# bGeigieNanoKit_V1_0r4.net
KiCad netlist of a schematic drawn in EAGLE
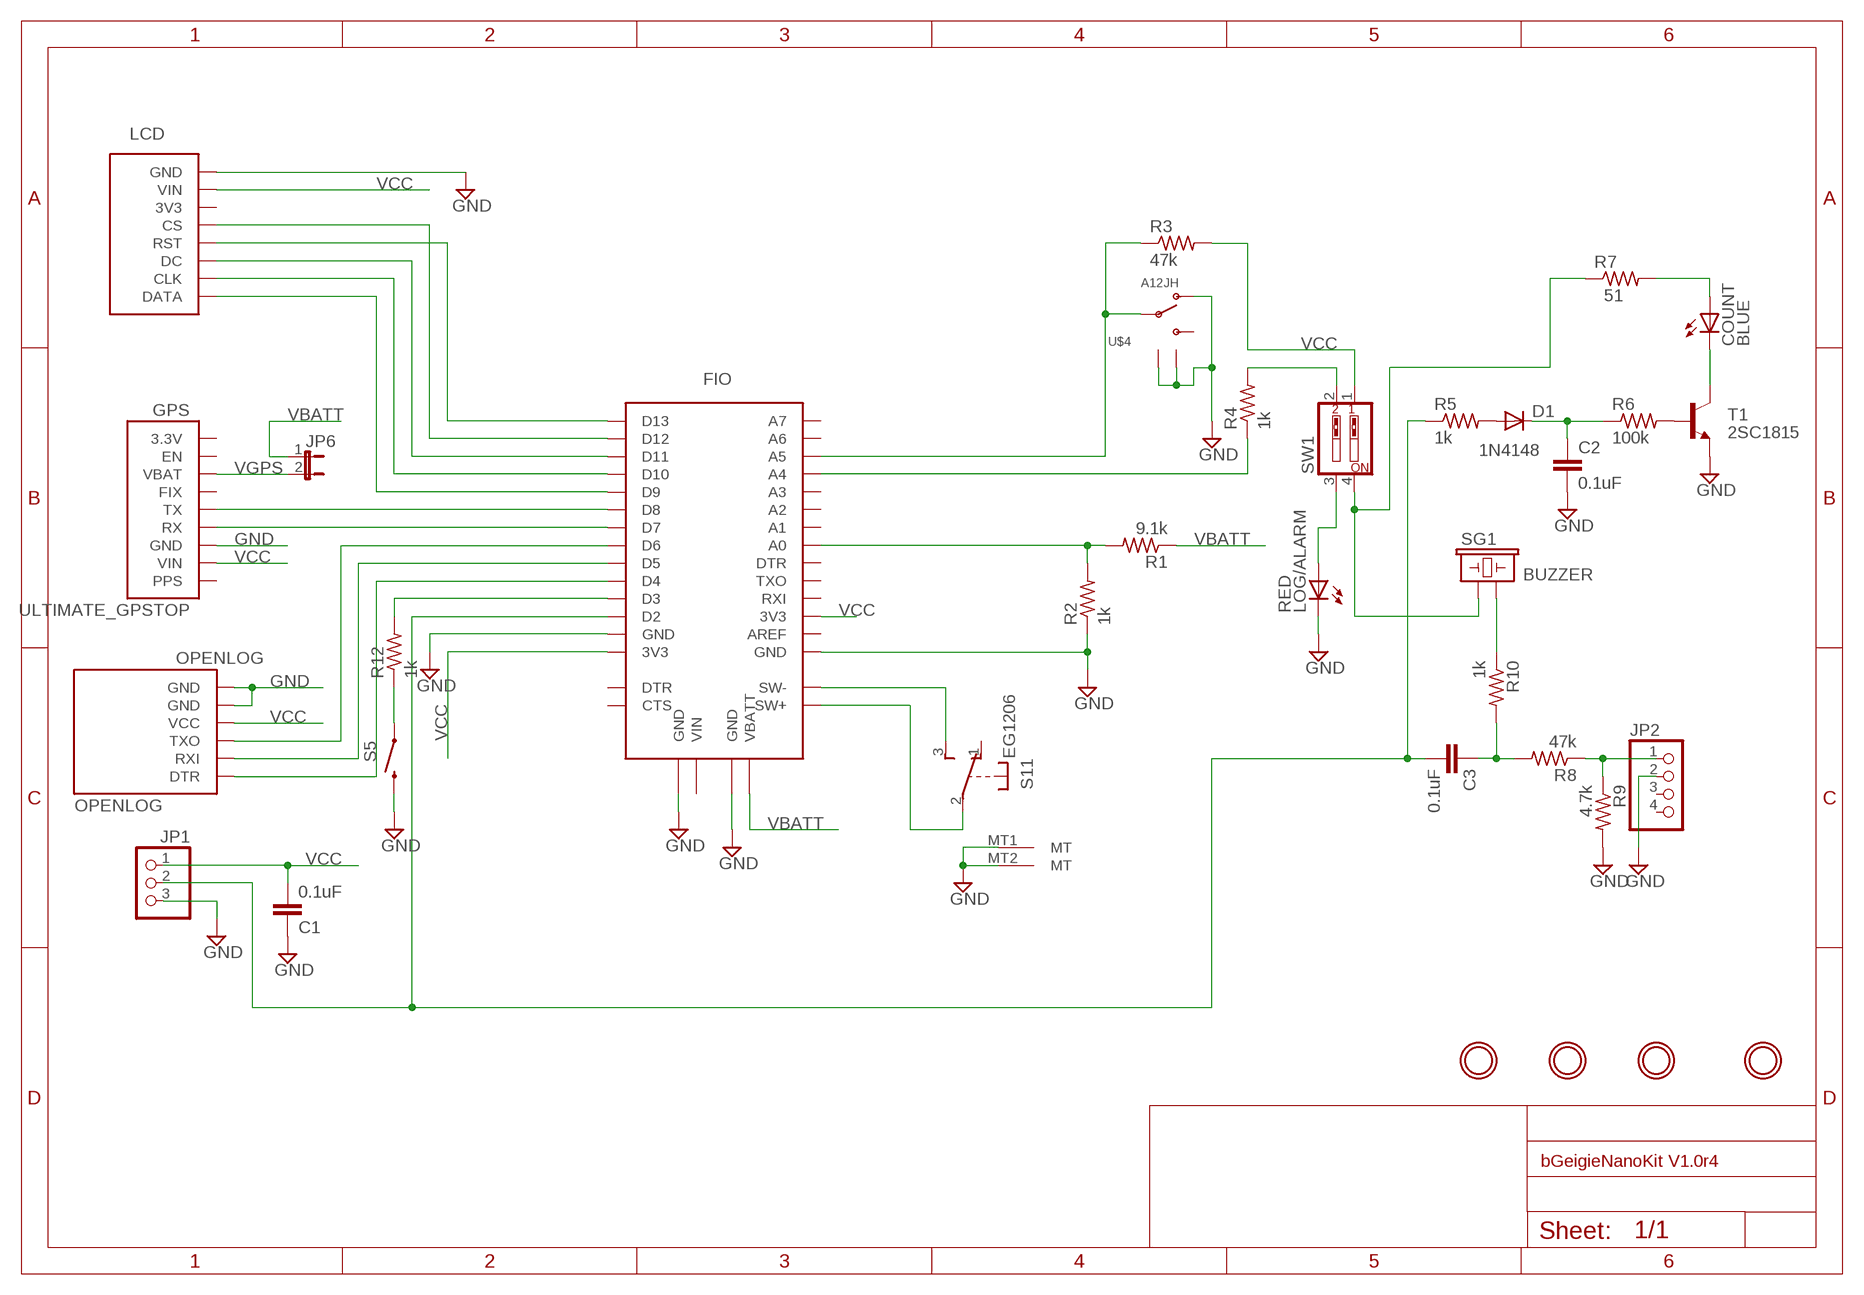
[diagram p0: schematic, sheet 1]

(export (version "E")
  (design (tool "Eeschema 10.0.6"))
  (components
    (comp (ref "C1")
      (value "0.1uF")
      (footprint "eagle-import:C025-024X044")
      (libsource (lib "eagle-import") (part "C-EU025-024X044"))
    )
    (comp (ref "C2")
      (value "0.1uF")
      (footprint "eagle-import:C025-024X044")
      (libsource (lib "eagle-import") (part "C-EU025-024X044"))
    )
    (comp (ref "C3")
      (value "0.1uF")
      (footprint "eagle-import:C025-024X044")
      (libsource (lib "eagle-import") (part "C-EU025-024X044"))
    )
    (comp (ref "COUNT")
      (value "BLUE")
      (footprint "eagle-import:LED3MM")
      (libsource (lib "eagle-import") (part "LED3MM"))
    )
    (comp (ref "D1")
      (value "1N4148")
      (footprint "eagle-import:DO35-7")
      (fields (field (name "D1") "1N4148"))
      (libsource (lib "eagle-import") (part "1N4148DO35-7"))
    )
    (comp (ref "FIO")
      (value "FIO_SOCKETBOT")
      (footprint "eagle-import:FIO_V23_SOCKET_BOT")
      (libsource (lib "eagle-import") (part "FIO_SOCKETBOT"))
    )
    (comp (ref "GPS")
      (value "ULTIMATE_GPSTOP")
      (footprint "eagle-import:ULTIMATE_GPS_V3_TOP")
      (libsource (lib "eagle-import") (part "ULTIMATE_GPSTOP"))
    )
    (comp (ref "JP1")
      (value "PINHD-1X3/90")
      (footprint "eagle-import:1X03_90")
      (libsource (lib "eagle-import") (part "PINHD-1X3/90"))
    )
    (comp (ref "JP2")
      (value "HEADER-1X4ROUND")
      (footprint "eagle-import:1X04_ROUND")
      (libsource (lib "eagle-import") (part "HEADER-1X4ROUND"))
    )
    (comp (ref "JP6")
      (value "JUMPER-2SMD-NC")
      (footprint "eagle-import:SJ_2S")
      (libsource (lib "eagle-import") (part "JUMPER-2SMD-NC"))
    )
    (comp (ref "LCD")
      (value "SSD1306_128X64_V2_LCD1.3IN_LEVER")
      (footprint "eagle-import:SSD1306_128X64_1.3IN_LCD_LEVER")
      (libsource (lib "eagle-import") (part "SSD1306_128X64_V2_LCD1.3IN_LEVER"))
    )
    (comp (ref "LOG/ALARM")
      (value "RED")
      (footprint "eagle-import:LED3MM")
      (libsource (lib "eagle-import") (part "LED3MM"))
    )
    (comp (ref "OPENLOG")
      (value "OPENLOG")
      (footprint "eagle-import:OPENLOG")
      (libsource (lib "eagle-import") (part "OPENLOG"))
    )
    (comp (ref "R1")
      (value "9.1k")
      (footprint "eagle-import:0207_10")
      (libsource (lib "eagle-import") (part "R-US_0207/10"))
    )
    (comp (ref "R2")
      (value "1k")
      (footprint "eagle-import:0207_10")
      (libsource (lib "eagle-import") (part "R-US_0207/10"))
    )
    (comp (ref "R3")
      (value "47k")
      (footprint "eagle-import:0207_10")
      (libsource (lib "eagle-import") (part "R-US_0207/10"))
    )
    (comp (ref "R4")
      (value "1k")
      (footprint "eagle-import:0207_10")
      (libsource (lib "eagle-import") (part "R-US_0207/10"))
    )
    (comp (ref "R5")
      (value "1k")
      (footprint "eagle-import:0207_10")
      (libsource (lib "eagle-import") (part "R-US_0207/10"))
    )
    (comp (ref "R6")
      (value "100k")
      (footprint "eagle-import:0207_10")
      (libsource (lib "eagle-import") (part "R-US_0207/10"))
    )
    (comp (ref "R7")
      (value "51")
      (footprint "eagle-import:0207_10")
      (libsource (lib "eagle-import") (part "R-US_0207/10"))
    )
    (comp (ref "R8")
      (value "47k")
      (footprint "eagle-import:0207_10")
      (libsource (lib "eagle-import") (part "R-US_0207/10"))
    )
    (comp (ref "R9")
      (value "4.7k")
      (footprint "eagle-import:0207_10")
      (libsource (lib "eagle-import") (part "R-US_0207/10"))
    )
    (comp (ref "R10")
      (value "1k")
      (footprint "eagle-import:0207_10")
      (libsource (lib "eagle-import") (part "R-US_0207/10"))
    )
    (comp (ref "R12")
      (value "1k")
      (footprint "eagle-import:0207_10")
      (libsource (lib "eagle-import") (part "R-US_0207/10"))
    )
    (comp (ref "S1")
      (value "EG1206")
      (footprint "eagle-import:EG1206")
      (libsource (lib "eagle-import") (part "EG1206"))
    )
    (comp (ref "S5")
      (value "SWITCH-MOMENTARY-2PTH")
      (footprint "eagle-import:TACTILE-PTH")
      (libsource (lib "eagle-import") (part "SWITCH-MOMENTARY-2PTH"))
    )
    (comp (ref "SG1")
      (value "BUZZER")
      (footprint "eagle-import:BUZZER-12MM")
      (libsource (lib "eagle-import") (part "BUZZERPTH"))
    )
    (comp (ref "SW1")
      (value "SW_DIP-2")
      (footprint "eagle-import:EDG-02")
      (libsource (lib "eagle-import") (part "SW_DIP-2"))
    )
    (comp (ref "T1")
      (value "2SC1815")
      (footprint "eagle-import:TO92-ECB")
      (libsource (lib "eagle-import") (part "2SC1815"))
    )
    (comp (ref "U$4")
      (value "A12JH")
      (footprint "eagle-import:A12AH")
      (libsource (lib "eagle-import") (part "A12JH"))
    )
    (comp (ref "U$6")
      (value "MOUNTINGHOLE3.0THIN")
      (footprint "eagle-import:MOUNTINGHOLE_3.0_PLATEDTHIN")
      (libsource (lib "eagle-import") (part "MOUNTINGHOLE3.0THIN"))
    )
    (comp (ref "U$7")
      (value "MOUNTINGHOLE3.0THIN")
      (footprint "eagle-import:MOUNTINGHOLE_3.0_PLATEDTHIN")
      (libsource (lib "eagle-import") (part "MOUNTINGHOLE3.0THIN"))
    )
    (comp (ref "U$8")
      (value "MOUNTINGHOLE3.0THIN")
      (footprint "eagle-import:MOUNTINGHOLE_3.0_PLATEDTHIN")
      (libsource (lib "eagle-import") (part "MOUNTINGHOLE3.0THIN"))
    )
    (comp (ref "U$9")
      (value "MOUNTINGHOLE3.0THIN")
      (footprint "eagle-import:MOUNTINGHOLE_3.0_PLATEDTHIN")
      (libsource (lib "eagle-import") (part "MOUNTINGHOLE3.0THIN"))
    )
  )
  (nets
    (net (code "1") (name "/3.3V") (class "Default")
      (node (ref "GPS") (pin "JP1$9") (pinfunction "3.3V_JP1$9") (pintype "power_in"))
    )
    (net (code "2") (name "/VBATT") (class "Default")
      (node (ref "FIO") (pin "JP2$2") (pinfunction "VBATT_JP2$2") (pintype "bidirectional"))
      (node (ref "JP6") (pin "1") (pinfunction "1_1") (pintype "passive"))
      (node (ref "R1") (pin "1") (pinfunction "1_1") (pintype "passive"))
    )
    (net (code "3") (name "/VCC") (class "Default")
      (node (ref "C1") (pin "2") (pinfunction "2_2") (pintype "passive"))
      (node (ref "FIO") (pin "JP1$1") (pinfunction "3V3_JP1$1") (pintype "power_in"))
      (node (ref "FIO") (pin "JP5$3") (pinfunction "3V3_JP5$3") (pintype "power_in"))
      (node (ref "GPS") (pin "JP1$2") (pinfunction "VIN_JP1$2") (pintype "power_in"))
      (node (ref "JP1") (pin "1") (pinfunction "1_1") (pintype "passive"))
      (node (ref "LCD") (pin "JP1$7") (pinfunction "VIN_JP1$7") (pintype "power_in"))
      (node (ref "OPENLOG") (pin "JP1$4") (pinfunction "VCC_JP1$4") (pintype "power_in"))
      (node (ref "R3") (pin "2") (pinfunction "2_2") (pintype "passive"))
      (node (ref "SW1") (pin "1") (pinfunction "1_1") (pintype "passive"))
    )
    (net (code "4") (name "/VGPS") (class "Default")
      (node (ref "GPS") (pin "JP1$7") (pinfunction "VBAT_JP1$7") (pintype "power_in"))
      (node (ref "JP6") (pin "2") (pinfunction "2_2") (pintype "passive"))
    )
    (net (code "5") (name "GND") (class "Default")
      (node (ref "C1") (pin "1") (pinfunction "1_1") (pintype "passive"))
      (node (ref "C2") (pin "2") (pinfunction "2_2") (pintype "passive"))
      (node (ref "FIO") (pin "JP1$2") (pinfunction "GND_JP1$2") (pintype "power_in"))
      (node (ref "FIO") (pin "JP2$1") (pinfunction "GND_JP2$1") (pintype "bidirectional"))
      (node (ref "FIO") (pin "JP5$1") (pinfunction "GND_JP5$1") (pintype "power_in"))
      (node (ref "FIO") (pin "JP6$1") (pinfunction "GND_JP6$1") (pintype "bidirectional"))
      (node (ref "GPS") (pin "JP1$3") (pinfunction "GND_JP1$3") (pintype "power_in"))
      (node (ref "GPS") (pin "U$8$P$1") (pinfunction "GND_U$8$P$1") (pintype "power_in"))
      (node (ref "GPS") (pin "U$9$P$1") (pinfunction "GND_U$9$P$1") (pintype "power_in"))
      (node (ref "JP1") (pin "3") (pinfunction "3_3") (pintype "passive"))
      (node (ref "JP2") (pin "2") (pinfunction "2_2") (pintype "passive"))
      (node (ref "LCD") (pin "JP1$8") (pinfunction "GND_JP1$8") (pintype "power_in"))
      (node (ref "LCD") (pin "U$23$P$1") (pinfunction "GND_U$23$P$1") (pintype "power_in"))
      (node (ref "LCD") (pin "U$26$P$1") (pinfunction "GND_U$26$P$1") (pintype "power_in"))
      (node (ref "LOG/ALARM") (pin "K") (pinfunction "C_K") (pintype "passive"))
      (node (ref "OPENLOG") (pin "JP1$5") (pinfunction "GND_JP1$5") (pintype "power_in"))
      (node (ref "OPENLOG") (pin "JP1$6") (pinfunction "GND_JP1$6") (pintype "power_in"))
      (node (ref "R2") (pin "1") (pinfunction "1_1") (pintype "passive"))
      (node (ref "R9") (pin "2") (pinfunction "2_2") (pintype "passive"))
      (node (ref "S1") (pin "MT1") (pinfunction "MT_MT1") (pintype "passive"))
      (node (ref "S1") (pin "MT2") (pinfunction "MT_MT2") (pintype "passive"))
      (node (ref "S5") (pin "3") (pinfunction "2_3") (pintype "passive"))
      (node (ref "T1") (pin "E") (pinfunction "E_E") (pintype "passive"))
      (node (ref "U$4") (pin "P$1") (pinfunction "P$1_P$1") (pintype "passive"))
      (node (ref "U$4") (pin "P$4") (pinfunction "GND_P$4") (pintype "power_in"))
      (node (ref "U$4") (pin "P$5") (pinfunction "GND_P$5") (pintype "power_in"))
    )
    (net (code "6") (name "Net-(C2-Pad1)") (class "Default")
      (node (ref "C2") (pin "1") (pinfunction "1_1") (pintype "passive"))
      (node (ref "D1") (pin "C") (pinfunction "C_C") (pintype "passive"))
      (node (ref "R6") (pin "1") (pinfunction "1_1") (pintype "passive"))
    )
    (net (code "7") (name "Net-(C3-Pad1)") (class "Default")
      (node (ref "C3") (pin "1") (pinfunction "1_1") (pintype "passive"))
      (node (ref "R10") (pin "2") (pinfunction "2_2") (pintype "passive"))
      (node (ref "R8") (pin "2") (pinfunction "2_2") (pintype "passive"))
    )
    (net (code "8") (name "Net-(COUNT-C)") (class "Default")
      (node (ref "COUNT") (pin "K") (pinfunction "C_K") (pintype "passive"))
      (node (ref "T1") (pin "C") (pinfunction "C_C") (pintype "passive"))
    )
    (net (code "9") (name "Net-(COUNT-PadA)") (class "Default")
      (node (ref "COUNT") (pin "A") (pinfunction "A_A") (pintype "passive"))
      (node (ref "R7") (pin "2") (pinfunction "2_2") (pintype "passive"))
    )
    (net (code "10") (name "Net-(D1-PadA)") (class "Default")
      (node (ref "D1") (pin "A") (pinfunction "A_A") (pintype "passive"))
      (node (ref "R5") (pin "2") (pinfunction "2_2") (pintype "passive"))
    )
    (net (code "11") (name "Net-(FIO-A0)") (class "Default")
      (node (ref "FIO") (pin "JP5$7") (pinfunction "A0_JP5$7") (pintype "bidirectional"))
      (node (ref "R1") (pin "2") (pinfunction "2_2") (pintype "passive"))
      (node (ref "R2") (pin "2") (pinfunction "2_2") (pintype "passive"))
    )
    (net (code "12") (name "Net-(FIO-A4)") (class "Default")
      (node (ref "FIO") (pin "JP5$11") (pinfunction "A4_JP5$11") (pintype "bidirectional"))
      (node (ref "R4") (pin "1") (pinfunction "1_1") (pintype "passive"))
    )
    (net (code "13") (name "Net-(FIO-A5)") (class "Default")
      (node (ref "FIO") (pin "JP5$12") (pinfunction "A5_JP5$12") (pintype "bidirectional"))
      (node (ref "R3") (pin "1") (pinfunction "1_1") (pintype "passive"))
      (node (ref "U$4") (pin "P$2") (pinfunction "P$2_P$2") (pintype "passive"))
    )
    (net (code "14") (name "Net-(FIO-D2)") (class "Default")
      (node (ref "C3") (pin "2") (pinfunction "2_2") (pintype "passive"))
      (node (ref "FIO") (pin "JP1$3") (pinfunction "D2_JP1$3") (pintype "bidirectional"))
      (node (ref "JP1") (pin "2") (pinfunction "2_2") (pintype "passive"))
      (node (ref "R5") (pin "1") (pinfunction "1_1") (pintype "passive"))
    )
    (net (code "15") (name "Net-(FIO-D3)") (class "Default")
      (node (ref "FIO") (pin "JP1$4") (pinfunction "D3_JP1$4") (pintype "bidirectional"))
      (node (ref "R12") (pin "2") (pinfunction "2_2") (pintype "passive"))
    )
    (net (code "16") (name "Net-(FIO-D4)") (class "Default")
      (node (ref "FIO") (pin "JP1$5") (pinfunction "D4_JP1$5") (pintype "bidirectional"))
      (node (ref "OPENLOG") (pin "JP1$1") (pinfunction "DTR_JP1$1") (pintype "input"))
    )
    (net (code "17") (name "Net-(FIO-D5)") (class "Default")
      (node (ref "FIO") (pin "JP1$6") (pinfunction "D5_JP1$6") (pintype "bidirectional"))
      (node (ref "OPENLOG") (pin "JP1$2") (pinfunction "RXI_JP1$2") (pintype "input"))
    )
    (net (code "18") (name "Net-(FIO-D6)") (class "Default")
      (node (ref "FIO") (pin "JP1$7") (pinfunction "D6_JP1$7") (pintype "bidirectional"))
      (node (ref "OPENLOG") (pin "JP1$3") (pinfunction "TXO_JP1$3") (pintype "output"))
    )
    (net (code "19") (name "Net-(FIO-D7)") (class "Default")
      (node (ref "FIO") (pin "JP1$8") (pinfunction "D7_JP1$8") (pintype "bidirectional"))
      (node (ref "GPS") (pin "JP1$4") (pinfunction "RX_JP1$4") (pintype "input"))
    )
    (net (code "20") (name "Net-(FIO-D8)") (class "Default")
      (node (ref "FIO") (pin "JP1$9") (pinfunction "D8_JP1$9") (pintype "bidirectional"))
      (node (ref "GPS") (pin "JP1$5") (pinfunction "TX_JP1$5") (pintype "output"))
    )
    (net (code "21") (name "Net-(FIO-D9)") (class "Default")
      (node (ref "FIO") (pin "JP1$10") (pinfunction "D9_JP1$10") (pintype "bidirectional"))
      (node (ref "LCD") (pin "JP1$1") (pinfunction "DATA_JP1$1") (pintype "bidirectional"))
    )
    (net (code "22") (name "Net-(FIO-D10)") (class "Default")
      (node (ref "FIO") (pin "JP1$11") (pinfunction "D10_JP1$11") (pintype "bidirectional"))
      (node (ref "LCD") (pin "JP1$2") (pinfunction "CLK_JP1$2") (pintype "bidirectional"))
    )
    (net (code "23") (name "Net-(FIO-D11)") (class "Default")
      (node (ref "FIO") (pin "JP1$12") (pinfunction "D11_JP1$12") (pintype "bidirectional"))
      (node (ref "LCD") (pin "JP1$3") (pinfunction "DC_JP1$3") (pintype "bidirectional"))
    )
    (net (code "24") (name "Net-(FIO-D12)") (class "Default")
      (node (ref "FIO") (pin "JP1$13") (pinfunction "D12_JP1$13") (pintype "bidirectional"))
      (node (ref "LCD") (pin "JP1$5") (pinfunction "CS_JP1$5") (pintype "bidirectional"))
    )
    (net (code "25") (name "Net-(FIO-D13)") (class "Default")
      (node (ref "FIO") (pin "JP1$14") (pinfunction "D13_JP1$14") (pintype "bidirectional"))
      (node (ref "LCD") (pin "JP1$4") (pinfunction "RST_JP1$4") (pintype "bidirectional"))
    )
    (net (code "26") (name "Net-(FIO-SW+)") (class "Default")
      (node (ref "FIO") (pin "JP7$2") (pinfunction "SW+_JP7$2") (pintype "bidirectional"))
      (node (ref "S1") (pin "2") (pinfunction "P_2") (pintype "passive"))
    )
    (net (code "27") (name "Net-(FIO-SW-)") (class "Default")
      (node (ref "FIO") (pin "JP7$1") (pinfunction "SW-_JP7$1") (pintype "bidirectional"))
      (node (ref "S1") (pin "3") (pinfunction "S_3") (pintype "passive"))
    )
    (net (code "28") (name "Net-(JP2-Pad1)") (class "Default")
      (node (ref "JP2") (pin "1") (pinfunction "1_1") (pintype "passive"))
      (node (ref "R8") (pin "1") (pinfunction "1_1") (pintype "passive"))
      (node (ref "R9") (pin "1") (pinfunction "1_1") (pintype "passive"))
    )
    (net (code "29") (name "Net-(LOG/ALARM-PadA)") (class "Default")
      (node (ref "LOG/ALARM") (pin "A") (pinfunction "A_A") (pintype "passive"))
      (node (ref "SW1") (pin "3") (pinfunction "3_3") (pintype "passive"))
    )
    (net (code "30") (name "Net-(R4-Pad2)") (class "Default")
      (node (ref "R4") (pin "2") (pinfunction "2_2") (pintype "passive"))
      (node (ref "SW1") (pin "2") (pinfunction "2_2") (pintype "passive"))
    )
    (net (code "31") (name "Net-(R6-Pad2)") (class "Default")
      (node (ref "R6") (pin "2") (pinfunction "2_2") (pintype "passive"))
      (node (ref "T1") (pin "B") (pinfunction "B_B") (pintype "passive"))
    )
    (net (code "32") (name "Net-(R12-Pad1)") (class "Default")
      (node (ref "R12") (pin "1") (pinfunction "1_1") (pintype "passive"))
      (node (ref "S5") (pin "1") (pinfunction "1_1") (pintype "passive"))
    )
    (net (code "33") (name "Net-(SG1-1)") (class "Default")
      (node (ref "R7") (pin "1") (pinfunction "1_1") (pintype "passive"))
      (node (ref "SG1") (pin "+") (pinfunction "1_+") (pintype "passive"))
      (node (ref "SW1") (pin "4") (pinfunction "4_4") (pintype "passive"))
    )
    (net (code "34") (name "Net-(SG1-2)") (class "Default")
      (node (ref "R10") (pin "1") (pinfunction "1_1") (pintype "passive"))
      (node (ref "SG1") (pin "-") (pinfunction "2_-") (pintype "passive"))
    )
    (net (code "35") (name "unconnected-(FIO-A1-PadJP5$8)") (class "Default")
      (node (ref "FIO") (pin "JP5$8") (pinfunction "A1_JP5$8") (pintype "bidirectional"))
    )
    (net (code "36") (name "unconnected-(FIO-A2-PadJP5$9)") (class "Default")
      (node (ref "FIO") (pin "JP5$9") (pinfunction "A2_JP5$9") (pintype "bidirectional"))
    )
    (net (code "37") (name "unconnected-(FIO-A3-PadJP5$10)") (class "Default")
      (node (ref "FIO") (pin "JP5$10") (pinfunction "A3_JP5$10") (pintype "bidirectional"))
    )
    (net (code "38") (name "unconnected-(FIO-A6-PadJP5$13)") (class "Default")
      (node (ref "FIO") (pin "JP5$13") (pinfunction "A6_JP5$13") (pintype "bidirectional"))
    )
    (net (code "39") (name "unconnected-(FIO-A7-PadJP5$14)") (class "Default")
      (node (ref "FIO") (pin "JP5$14") (pinfunction "A7_JP5$14") (pintype "bidirectional"))
    )
    (net (code "40") (name "unconnected-(FIO-AREF-PadJP5$2)") (class "Default")
      (node (ref "FIO") (pin "JP5$2") (pinfunction "AREF_JP5$2") (pintype "output"))
    )
    (net (code "41") (name "unconnected-(FIO-CTS-PadJP8$1)") (class "Default")
      (node (ref "FIO") (pin "JP8$1") (pinfunction "CTS_JP8$1") (pintype "bidirectional"))
    )
    (net (code "42") (name "unconnected-(FIO-DTR-PadJP5$6)") (class "Default")
      (node (ref "FIO") (pin "JP5$6") (pinfunction "DTR_JP5$6") (pintype "input"))
    )
    (net (code "43") (name "unconnected-(FIO-DTR-PadJP9$1)") (class "Default")
      (node (ref "FIO") (pin "JP9$1") (pinfunction "DTR_JP9$1") (pintype "bidirectional"))
    )
    (net (code "44") (name "unconnected-(FIO-RXI-PadJP5$4)") (class "Default")
      (node (ref "FIO") (pin "JP5$4") (pinfunction "RXI_JP5$4") (pintype "input"))
    )
    (net (code "45") (name "unconnected-(FIO-TXO-PadJP5$5)") (class "Default")
      (node (ref "FIO") (pin "JP5$5") (pinfunction "TXO_JP5$5") (pintype "output"))
    )
    (net (code "46") (name "unconnected-(FIO-VIN-PadJP6$2)") (class "Default")
      (node (ref "FIO") (pin "JP6$2") (pinfunction "VIN_JP6$2") (pintype "bidirectional"))
    )
    (net (code "47") (name "unconnected-(GPS-EN-PadJP1$8)") (class "Default")
      (node (ref "GPS") (pin "JP1$8") (pinfunction "EN_JP1$8") (pintype "input"))
    )
    (net (code "48") (name "unconnected-(GPS-FIX-PadJP1$6)") (class "Default")
      (node (ref "GPS") (pin "JP1$6") (pinfunction "FIX_JP1$6") (pintype "output"))
    )
    (net (code "49") (name "unconnected-(GPS-PPS-PadJP1$1)") (class "Default")
      (node (ref "GPS") (pin "JP1$1") (pinfunction "PPS_JP1$1") (pintype "output"))
    )
    (net (code "50") (name "unconnected-(JP2-Pad3)") (class "Default")
      (node (ref "JP2") (pin "3") (pinfunction "3_3") (pintype "passive"))
    )
    (net (code "51") (name "unconnected-(JP2-Pad4)") (class "Default")
      (node (ref "JP2") (pin "4") (pinfunction "4_4") (pintype "passive"))
    )
    (net (code "52") (name "unconnected-(LCD-3V3-PadJP1$6)") (class "Default")
      (node (ref "LCD") (pin "JP1$6") (pinfunction "3V3_JP1$6") (pintype "bidirectional"))
    )
    (net (code "53") (name "unconnected-(S1A-O-Pad1)") (class "Default")
      (node (ref "S1") (pin "1") (pinfunction "O_1") (pintype "passive"))
    )
    (net (code "54") (name "unconnected-(U$4-PadP$3)") (class "Default")
      (node (ref "U$4") (pin "P$3") (pinfunction "P$3_P$3") (pintype "passive"))
    )
  )
)
